# block_reset.net
KiCad netlist of a schematic drawn in EAGLE
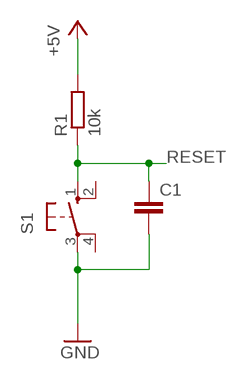
[diagram p0: schematic, sheet 1]

(export (version "E")
  (design (tool "Eeschema 10.0.6"))
  (components
    (comp (ref "C1")
      (value "C-EU050-024X044")
      (footprint "eagle-import:C050-024X044")
      (libsource (lib "eagle-import") (part "C-EU050-024X044"))
    )
    (comp (ref "R1")
      (value "10k")
      (footprint "eagle-import:0207_10")
      (libsource (lib "eagle-import") (part "R-EU_0207/10"))
    )
    (comp (ref "S1")
      (value "10-XX")
      (footprint "eagle-import:B3F-10XX")
      (fields (field (name "MPN") "B3F-1000"))
      (libsource (lib "eagle-import") (part "10-XX"))
    )
  )
  (nets
    (net (code "1") (name "+5V") (class "Default")
      (node (ref "R1") (pin "2") (pinfunction "2_2") (pintype "passive"))
    )
    (net (code "2") (name "/RESET") (class "Default")
      (node (ref "C1") (pin "1") (pinfunction "1_1") (pintype "passive"))
      (node (ref "R1") (pin "1") (pinfunction "1_1") (pintype "passive"))
      (node (ref "S1") (pin "1") (pinfunction "S_1") (pintype "passive"))
    )
    (net (code "3") (name "GND") (class "Default")
      (node (ref "C1") (pin "2") (pinfunction "2_2") (pintype "passive"))
      (node (ref "S1") (pin "3") (pinfunction "P_3") (pintype "passive"))
    )
    (net (code "4") (name "unconnected-(S1-P1-Pad4)") (class "Default")
      (node (ref "S1") (pin "4") (pinfunction "P1_4") (pintype "passive"))
    )
    (net (code "5") (name "unconnected-(S1-S1-Pad2)") (class "Default")
      (node (ref "S1") (pin "2") (pinfunction "S1_2") (pintype "passive"))
    )
  )
)
